# UAS_SENSOR.net
KiCad netlist of a schematic drawn in EasyEDA
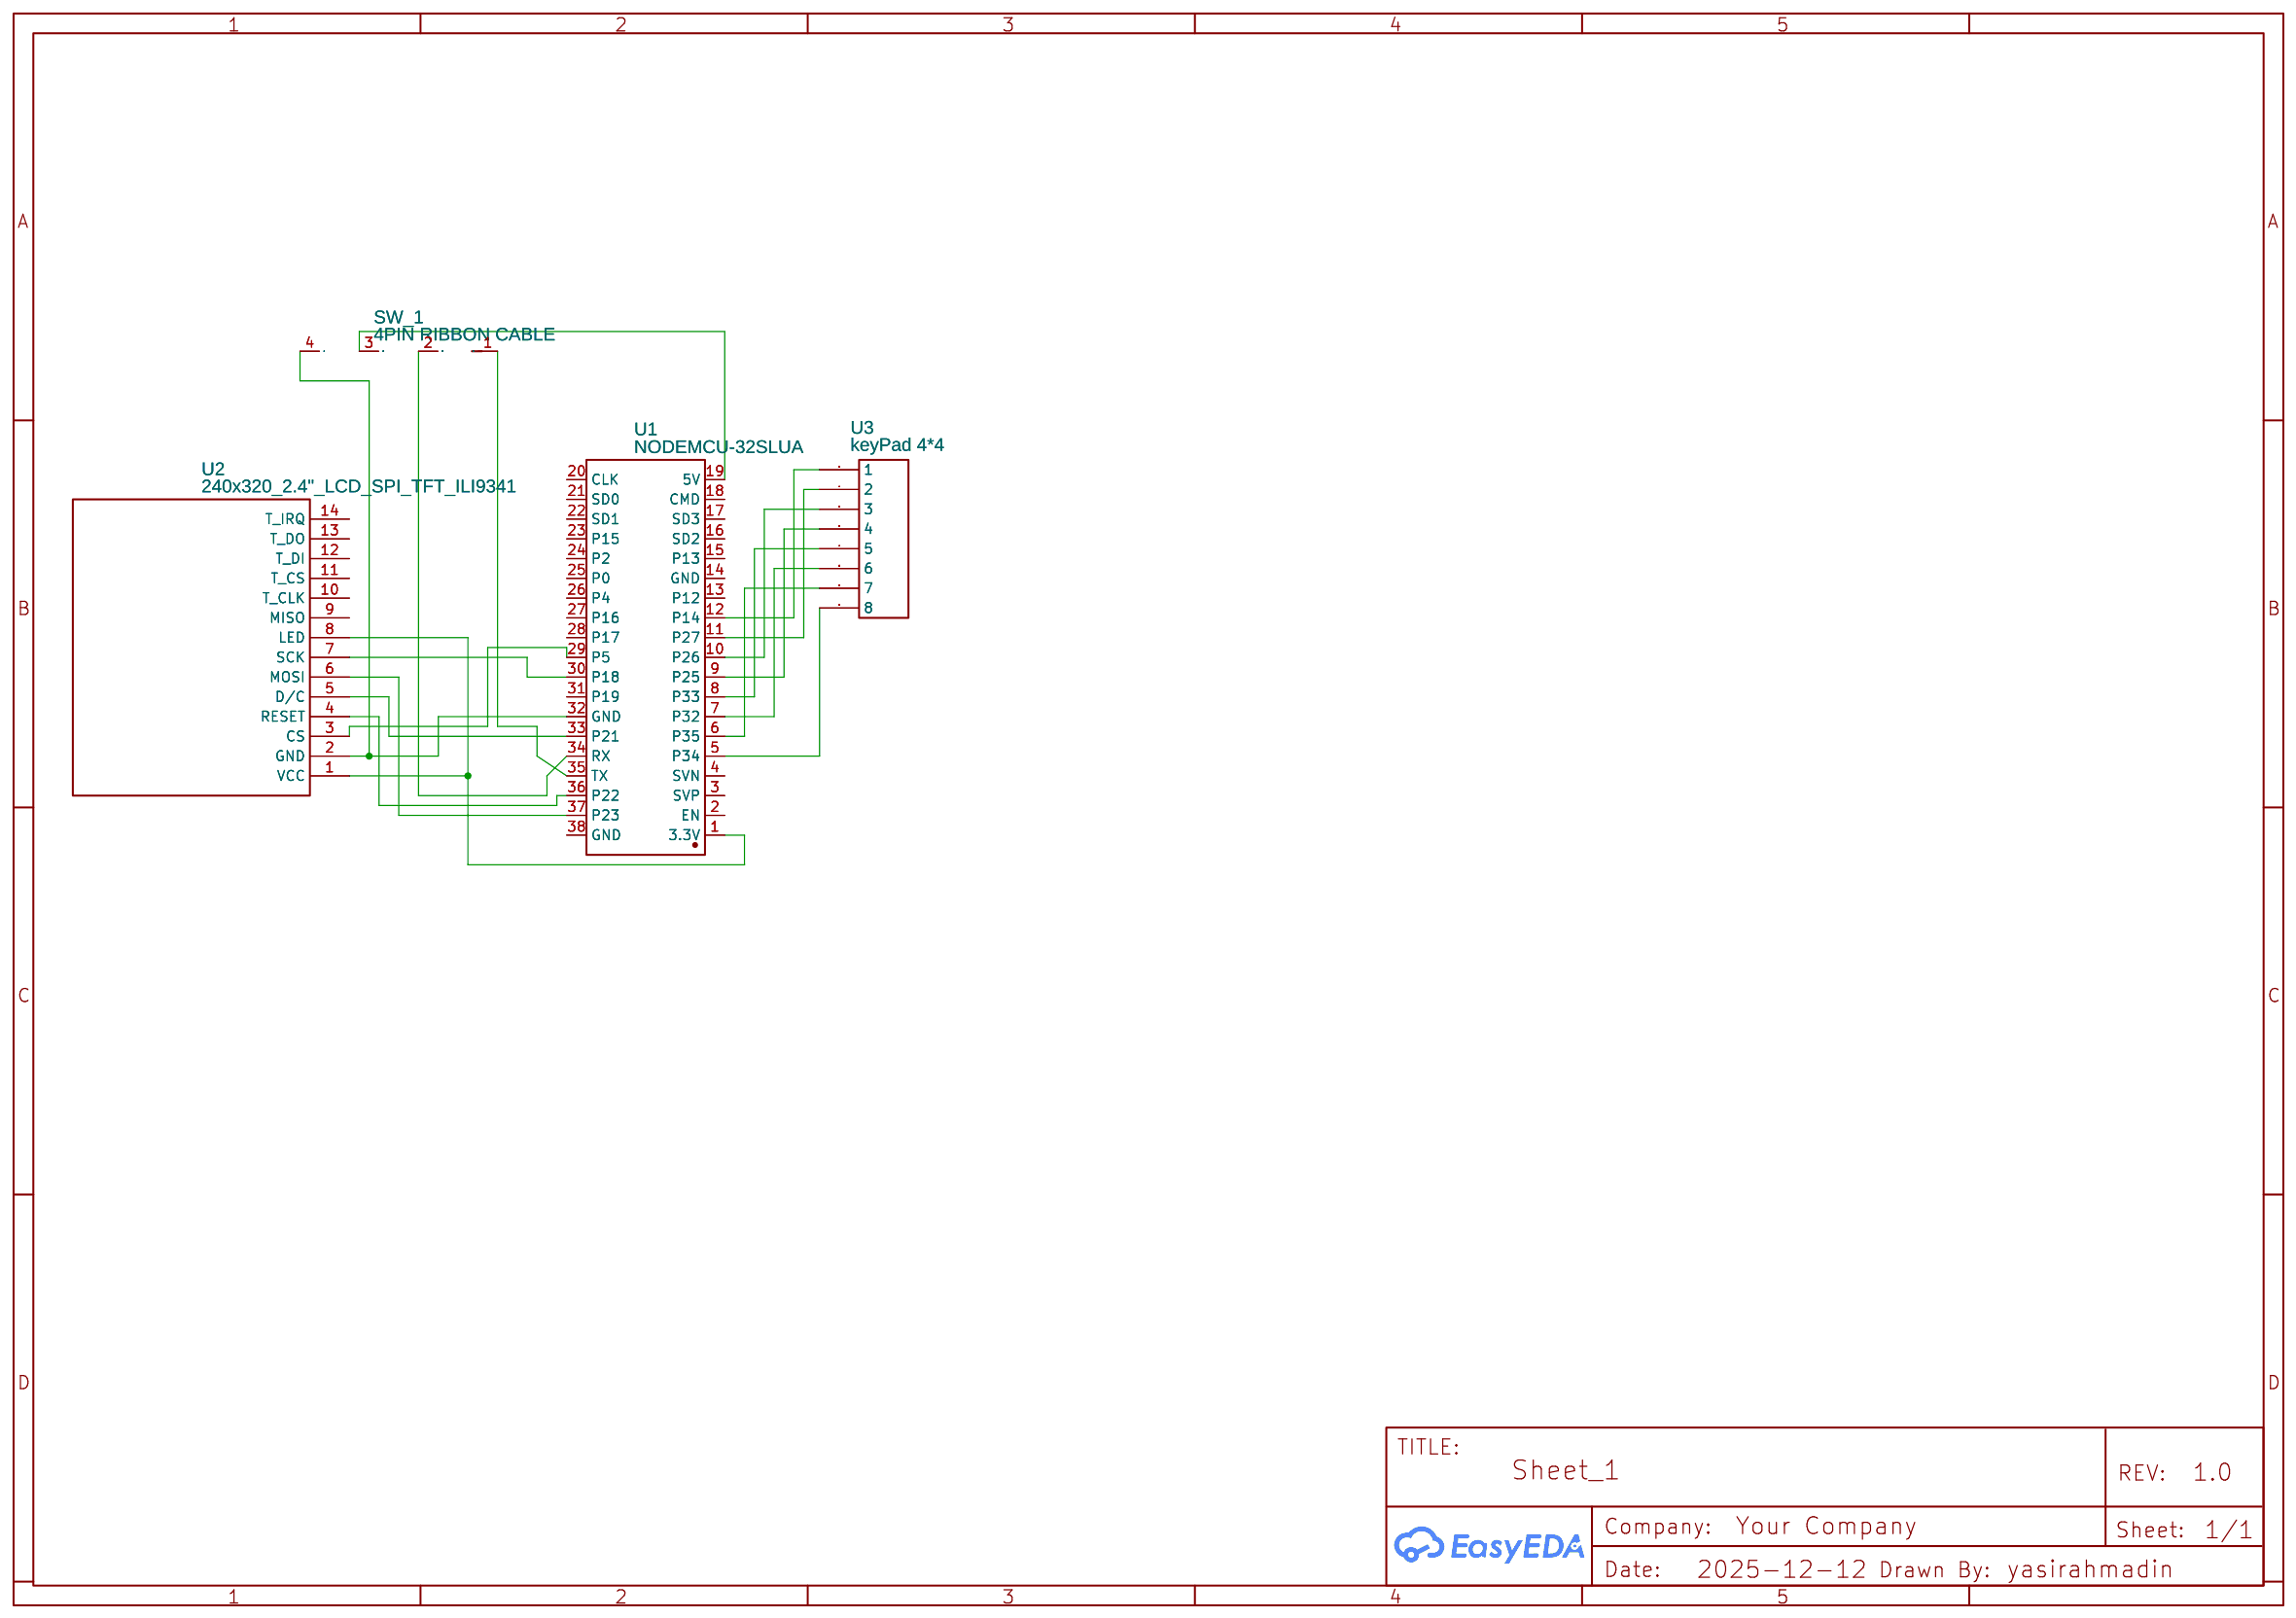
[diagram p0: schematic sheet]

(export (version "E")
  (design (tool "Eeschema 10.0.6"))
  (components
    (comp (ref "SW_1") (value "4PIN RIBBON CABLE") (libsource (lib "") (part "4PIN RIBBON CABLE")))
    (comp (ref "U1")
      (value "NODEMCU-32SLUA")
      (fields
        (field (name "Manufacturer Part") "NodeMCU-32SLua")
        (field (name "Manufacturer") "Ai-Thinker(安信可)")
      )
      (libsource (lib "") (part "NODEMCU-32SLUA"))
    )
    (comp (ref "U2")
      (value "240x320_2.4\"_LCD_SPI_TFT_ILI9341")
      (libsource (lib "") (part "240x320_2.4{dblquote}_LCD_SPI_TFT_ILI9341"))
    )
    (comp (ref "U3") (value "keyPad 4*4") (libsource (lib "") (part "keyPad 4*4")))
  )
  (nets
    (net (code "1") (name "Net-(U1-3.3V)") (class "Default")
      (node (ref "U1") (pin "1") (pinfunction "3.3V_1") (pintype "unspecified"))
      (node (ref "U2") (pin "1") (pinfunction "VCC_1") (pintype "unspecified"))
      (node (ref "U2") (pin "8") (pinfunction "LED_8") (pintype "unspecified"))
    )
    (net (code "2") (name "Net-(U1-5V)") (class "Default")
      (node (ref "SW_1") (pin "3") (pinfunction "3_3") (pintype "bidirectional"))
      (node (ref "U1") (pin "19") (pinfunction "5V_19") (pintype "unspecified"))
    )
    (net (code "3") (name "Net-(U1-P5)") (class "Default")
      (node (ref "U1") (pin "29") (pinfunction "P5_29") (pintype "unspecified"))
      (node (ref "U2") (pin "3") (pinfunction "CS_3") (pintype "unspecified"))
    )
    (net (code "4") (name "Net-(U1-P14)") (class "Default")
      (node (ref "U1") (pin "12") (pinfunction "P14_12") (pintype "unspecified"))
      (node (ref "U3") (pin "3") (pinfunction "1_3") (pintype "unspecified"))
    )
    (net (code "5") (name "Net-(U1-P18)") (class "Default")
      (node (ref "U1") (pin "30") (pinfunction "P18_30") (pintype "unspecified"))
      (node (ref "U2") (pin "7") (pinfunction "SCK_7") (pintype "unspecified"))
    )
    (net (code "6") (name "Net-(U1-P21)") (class "Default")
      (node (ref "U1") (pin "33") (pinfunction "P21_33") (pintype "unspecified"))
      (node (ref "U2") (pin "5") (pinfunction "D/C_5") (pintype "unspecified"))
    )
    (net (code "7") (name "Net-(U1-P22)") (class "Default")
      (node (ref "U1") (pin "36") (pinfunction "P22_36") (pintype "unspecified"))
      (node (ref "U2") (pin "4") (pinfunction "RESET_4") (pintype "unspecified"))
    )
    (net (code "8") (name "Net-(U1-P23)") (class "Default")
      (node (ref "U1") (pin "37") (pinfunction "P23_37") (pintype "unspecified"))
      (node (ref "U2") (pin "6") (pinfunction "MOSI_6") (pintype "unspecified"))
    )
    (net (code "9") (name "Net-(U1-P25)") (class "Default")
      (node (ref "U1") (pin "9") (pinfunction "P25_9") (pintype "unspecified"))
      (node (ref "U3") (pin "6") (pinfunction "4_6") (pintype "unspecified"))
    )
    (net (code "10") (name "Net-(U1-P26)") (class "Default")
      (node (ref "U1") (pin "10") (pinfunction "P26_10") (pintype "unspecified"))
      (node (ref "U3") (pin "5") (pinfunction "3_5") (pintype "unspecified"))
    )
    (net (code "11") (name "Net-(U1-P27)") (class "Default")
      (node (ref "U1") (pin "11") (pinfunction "P27_11") (pintype "unspecified"))
      (node (ref "U3") (pin "4") (pinfunction "2_4") (pintype "unspecified"))
    )
    (net (code "12") (name "Net-(U1-P32)") (class "Default")
      (node (ref "U1") (pin "7") (pinfunction "P32_7") (pintype "unspecified"))
      (node (ref "U3") (pin "8") (pinfunction "6_8") (pintype "unspecified"))
    )
    (net (code "13") (name "Net-(U1-P33)") (class "Default")
      (node (ref "U1") (pin "8") (pinfunction "P33_8") (pintype "unspecified"))
      (node (ref "U3") (pin "7") (pinfunction "5_7") (pintype "unspecified"))
    )
    (net (code "14") (name "Net-(U1-P34)") (class "Default")
      (node (ref "U1") (pin "5") (pinfunction "P34_5") (pintype "unspecified"))
      (node (ref "U3") (pin "10") (pinfunction "8_10") (pintype "unspecified"))
    )
    (net (code "15") (name "Net-(U1-P35)") (class "Default")
      (node (ref "U1") (pin "6") (pinfunction "P35_6") (pintype "unspecified"))
      (node (ref "U3") (pin "9") (pinfunction "7_9") (pintype "unspecified"))
    )
    (net (code "16") (name "Net-(U1-RX)") (class "Default")
      (node (ref "SW_1") (pin "2") (pinfunction "2_2") (pintype "bidirectional"))
      (node (ref "U1") (pin "34") (pinfunction "RX_34") (pintype "unspecified"))
    )
    (net (code "17") (name "Net-(U1-TX)") (class "Default")
      (node (ref "SW_1") (pin "1") (pinfunction "1_1") (pintype "bidirectional"))
      (node (ref "U1") (pin "35") (pinfunction "TX_35") (pintype "unspecified"))
    )
    (net (code "18") (name "Net-(U2-GND)") (class "Default")
      (node (ref "SW_1") (pin "4") (pinfunction "4_4") (pintype "bidirectional"))
      (node (ref "U1") (pin "32") (pinfunction "GND_32") (pintype "unspecified"))
      (node (ref "U2") (pin "2") (pinfunction "GND_2") (pintype "unspecified"))
    )
    (net (code "19") (name "unconnected-(U1-CLK-Pad20)") (class "Default")
      (node (ref "U1") (pin "20") (pinfunction "CLK_20") (pintype "unspecified"))
    )
    (net (code "20") (name "unconnected-(U1-CMD-Pad18)") (class "Default")
      (node (ref "U1") (pin "18") (pinfunction "CMD_18") (pintype "unspecified"))
    )
    (net (code "21") (name "unconnected-(U1-EN-Pad2)") (class "Default")
      (node (ref "U1") (pin "2") (pinfunction "EN_2") (pintype "unspecified"))
    )
    (net (code "22") (name "unconnected-(U1-GND-Pad14)") (class "Default")
      (node (ref "U1") (pin "14") (pinfunction "GND_14") (pintype "unspecified"))
    )
    (net (code "23") (name "unconnected-(U1-GND-Pad38)") (class "Default")
      (node (ref "U1") (pin "38") (pinfunction "GND_38") (pintype "unspecified"))
    )
    (net (code "24") (name "unconnected-(U1-P0-Pad25)") (class "Default")
      (node (ref "U1") (pin "25") (pinfunction "P0_25") (pintype "unspecified"))
    )
    (net (code "25") (name "unconnected-(U1-P2-Pad24)") (class "Default")
      (node (ref "U1") (pin "24") (pinfunction "P2_24") (pintype "unspecified"))
    )
    (net (code "26") (name "unconnected-(U1-P4-Pad26)") (class "Default")
      (node (ref "U1") (pin "26") (pinfunction "P4_26") (pintype "unspecified"))
    )
    (net (code "27") (name "unconnected-(U1-P12-Pad13)") (class "Default")
      (node (ref "U1") (pin "13") (pinfunction "P12_13") (pintype "unspecified"))
    )
    (net (code "28") (name "unconnected-(U1-P13-Pad15)") (class "Default")
      (node (ref "U1") (pin "15") (pinfunction "P13_15") (pintype "unspecified"))
    )
    (net (code "29") (name "unconnected-(U1-P15-Pad23)") (class "Default")
      (node (ref "U1") (pin "23") (pinfunction "P15_23") (pintype "unspecified"))
    )
    (net (code "30") (name "unconnected-(U1-P16-Pad27)") (class "Default")
      (node (ref "U1") (pin "27") (pinfunction "P16_27") (pintype "unspecified"))
    )
    (net (code "31") (name "unconnected-(U1-P17-Pad28)") (class "Default")
      (node (ref "U1") (pin "28") (pinfunction "P17_28") (pintype "unspecified"))
    )
    (net (code "32") (name "unconnected-(U1-P19-Pad31)") (class "Default")
      (node (ref "U1") (pin "31") (pinfunction "P19_31") (pintype "unspecified"))
    )
    (net (code "33") (name "unconnected-(U1-SD0-Pad21)") (class "Default")
      (node (ref "U1") (pin "21") (pinfunction "SD0_21") (pintype "unspecified"))
    )
    (net (code "34") (name "unconnected-(U1-SD1-Pad22)") (class "Default")
      (node (ref "U1") (pin "22") (pinfunction "SD1_22") (pintype "unspecified"))
    )
    (net (code "35") (name "unconnected-(U1-SD2-Pad16)") (class "Default")
      (node (ref "U1") (pin "16") (pinfunction "SD2_16") (pintype "unspecified"))
    )
    (net (code "36") (name "unconnected-(U1-SD3-Pad17)") (class "Default")
      (node (ref "U1") (pin "17") (pinfunction "SD3_17") (pintype "unspecified"))
    )
    (net (code "37") (name "unconnected-(U1-SVN-Pad4)") (class "Default")
      (node (ref "U1") (pin "4") (pinfunction "SVN_4") (pintype "unspecified"))
    )
    (net (code "38") (name "unconnected-(U1-SVP-Pad3)") (class "Default")
      (node (ref "U1") (pin "3") (pinfunction "SVP_3") (pintype "unspecified"))
    )
    (net (code "39") (name "unconnected-(U2-MISO-Pad9)") (class "Default")
      (node (ref "U2") (pin "9") (pinfunction "MISO_9") (pintype "unspecified"))
    )
    (net (code "40") (name "unconnected-(U2-T_CLK-Pad10)") (class "Default")
      (node (ref "U2") (pin "10") (pinfunction "T_CLK_10") (pintype "unspecified"))
    )
    (net (code "41") (name "unconnected-(U2-T_CS-Pad11)") (class "Default")
      (node (ref "U2") (pin "11") (pinfunction "T_CS_11") (pintype "unspecified"))
    )
    (net (code "42") (name "unconnected-(U2-T_DI-Pad12)") (class "Default")
      (node (ref "U2") (pin "12") (pinfunction "T_DI_12") (pintype "unspecified"))
    )
    (net (code "43") (name "unconnected-(U2-T_DO-Pad13)") (class "Default")
      (node (ref "U2") (pin "13") (pinfunction "T_DO_13") (pintype "unspecified"))
    )
    (net (code "44") (name "unconnected-(U2-T_IRQ-Pad14)") (class "Default")
      (node (ref "U2") (pin "14") (pinfunction "T_IRQ_14") (pintype "unspecified"))
    )
  )
)
